# encoder.net
KiCad netlist of a schematic drawn in EAGLE
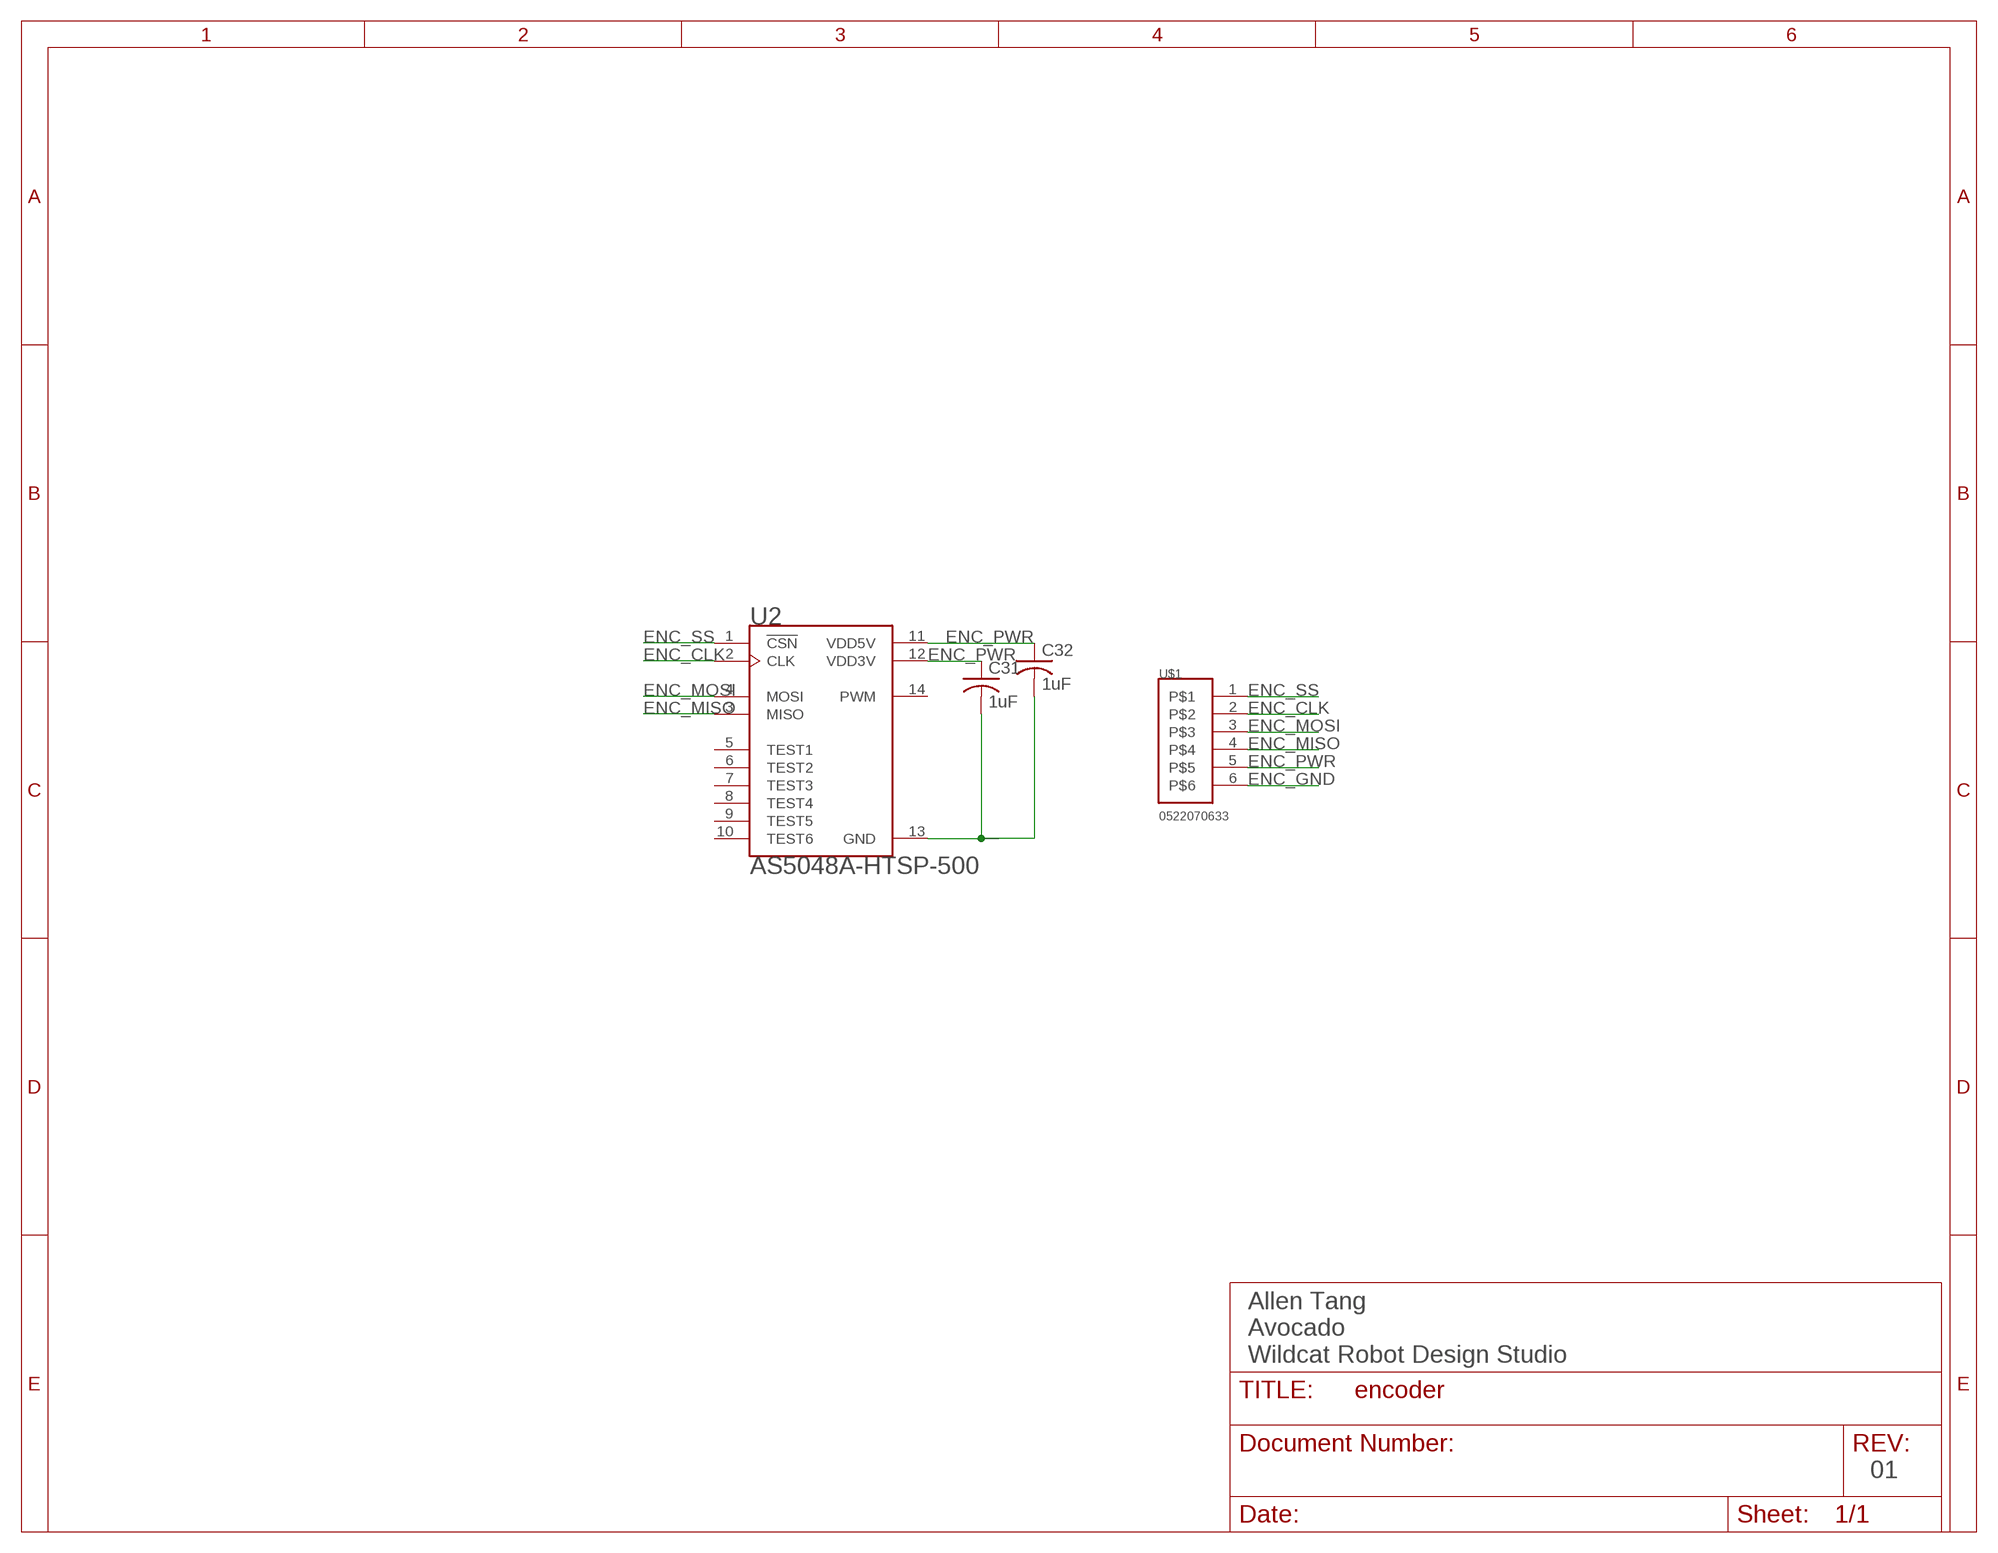
[diagram p0: schematic, sheet 1]

(export (version "E")
  (design (tool "Eeschema 10.0.6"))
  (components
    (comp (ref "C31")
      (value "1uF")
      (footprint "eagle-import:C0805")
      (libsource (lib "eagle-import") (part "C-USC0805"))
    )
    (comp (ref "C32")
      (value "1uF")
      (footprint "eagle-import:C0805")
      (libsource (lib "eagle-import") (part "C-USC0805"))
    )
    (comp (ref "U$1")
      (value "0522070633")
      (footprint "eagle-import:1MM-FPC-6PIN")
      (libsource (lib "eagle-import") (part "0522070633"))
    )
    (comp (ref "U2")
      (value "AS5048A-HTSP-500")
      (footprint "eagle-import:SOP65P640X120-14N")
      (fields (field (name "MF") "ams"))
      (libsource (lib "eagle-import") (part "AS5048A-HTSP-500"))
    )
  )
  (nets
    (net (code "1") (name "/ENC_CLK") (class "Default")
      (node (ref "U$1") (pin "2") (pinfunction "P$2_2") (pintype "bidirectional"))
      (node (ref "U2") (pin "2") (pinfunction "CLK_2") (pintype "input"))
    )
    (net (code "2") (name "/ENC_GND") (class "Default")
      (node (ref "C31") (pin "2") (pinfunction "2_2") (pintype "passive"))
      (node (ref "C32") (pin "2") (pinfunction "2_2") (pintype "passive"))
      (node (ref "U$1") (pin "6") (pinfunction "P$6_6") (pintype "bidirectional"))
      (node (ref "U2") (pin "13") (pinfunction "GND_13") (pintype "passive"))
    )
    (net (code "3") (name "/ENC_MISO") (class "Default")
      (node (ref "U$1") (pin "4") (pinfunction "P$4_4") (pintype "bidirectional"))
      (node (ref "U2") (pin "3") (pinfunction "MISO_3") (pintype "bidirectional"))
    )
    (net (code "4") (name "/ENC_MOSI") (class "Default")
      (node (ref "U$1") (pin "3") (pinfunction "P$3_3") (pintype "bidirectional"))
      (node (ref "U2") (pin "4") (pinfunction "MOSI_4") (pintype "input"))
    )
    (net (code "5") (name "/ENC_PWR") (class "Default")
      (node (ref "C31") (pin "1") (pinfunction "1_1") (pintype "passive"))
      (node (ref "C32") (pin "1") (pinfunction "1_1") (pintype "passive"))
      (node (ref "U$1") (pin "5") (pinfunction "P$5_5") (pintype "bidirectional"))
      (node (ref "U2") (pin "11") (pinfunction "VDD5V_11") (pintype "power_in"))
      (node (ref "U2") (pin "12") (pinfunction "VDD3V_12") (pintype "power_in"))
    )
    (net (code "6") (name "/ENC_SS") (class "Default")
      (node (ref "U$1") (pin "1") (pinfunction "P$1_1") (pintype "bidirectional"))
      (node (ref "U2") (pin "1") (pinfunction "~{CSN}_1") (pintype "input"))
    )
    (net (code "7") (name "unconnected-(U2-PWM-Pad14)") (class "Default")
      (node (ref "U2") (pin "14") (pinfunction "PWM_14") (pintype "output"))
    )
    (net (code "8") (name "unconnected-(U2-TEST1-Pad5)") (class "Default")
      (node (ref "U2") (pin "5") (pinfunction "TEST1_5") (pintype "bidirectional"))
    )
    (net (code "9") (name "unconnected-(U2-TEST2-Pad6)") (class "Default")
      (node (ref "U2") (pin "6") (pinfunction "TEST2_6") (pintype "bidirectional"))
    )
    (net (code "10") (name "unconnected-(U2-TEST3-Pad7)") (class "Default")
      (node (ref "U2") (pin "7") (pinfunction "TEST3_7") (pintype "bidirectional"))
    )
    (net (code "11") (name "unconnected-(U2-TEST4-Pad8)") (class "Default")
      (node (ref "U2") (pin "8") (pinfunction "TEST4_8") (pintype "bidirectional"))
    )
    (net (code "12") (name "unconnected-(U2-TEST5-Pad9)") (class "Default")
      (node (ref "U2") (pin "9") (pinfunction "TEST5_9") (pintype "bidirectional"))
    )
    (net (code "13") (name "unconnected-(U2-TEST6-Pad10)") (class "Default")
      (node (ref "U2") (pin "10") (pinfunction "TEST6_10") (pintype "bidirectional"))
    )
  )
)
